# joystick.net
KiCad netlist of a schematic drawn in EAGLE
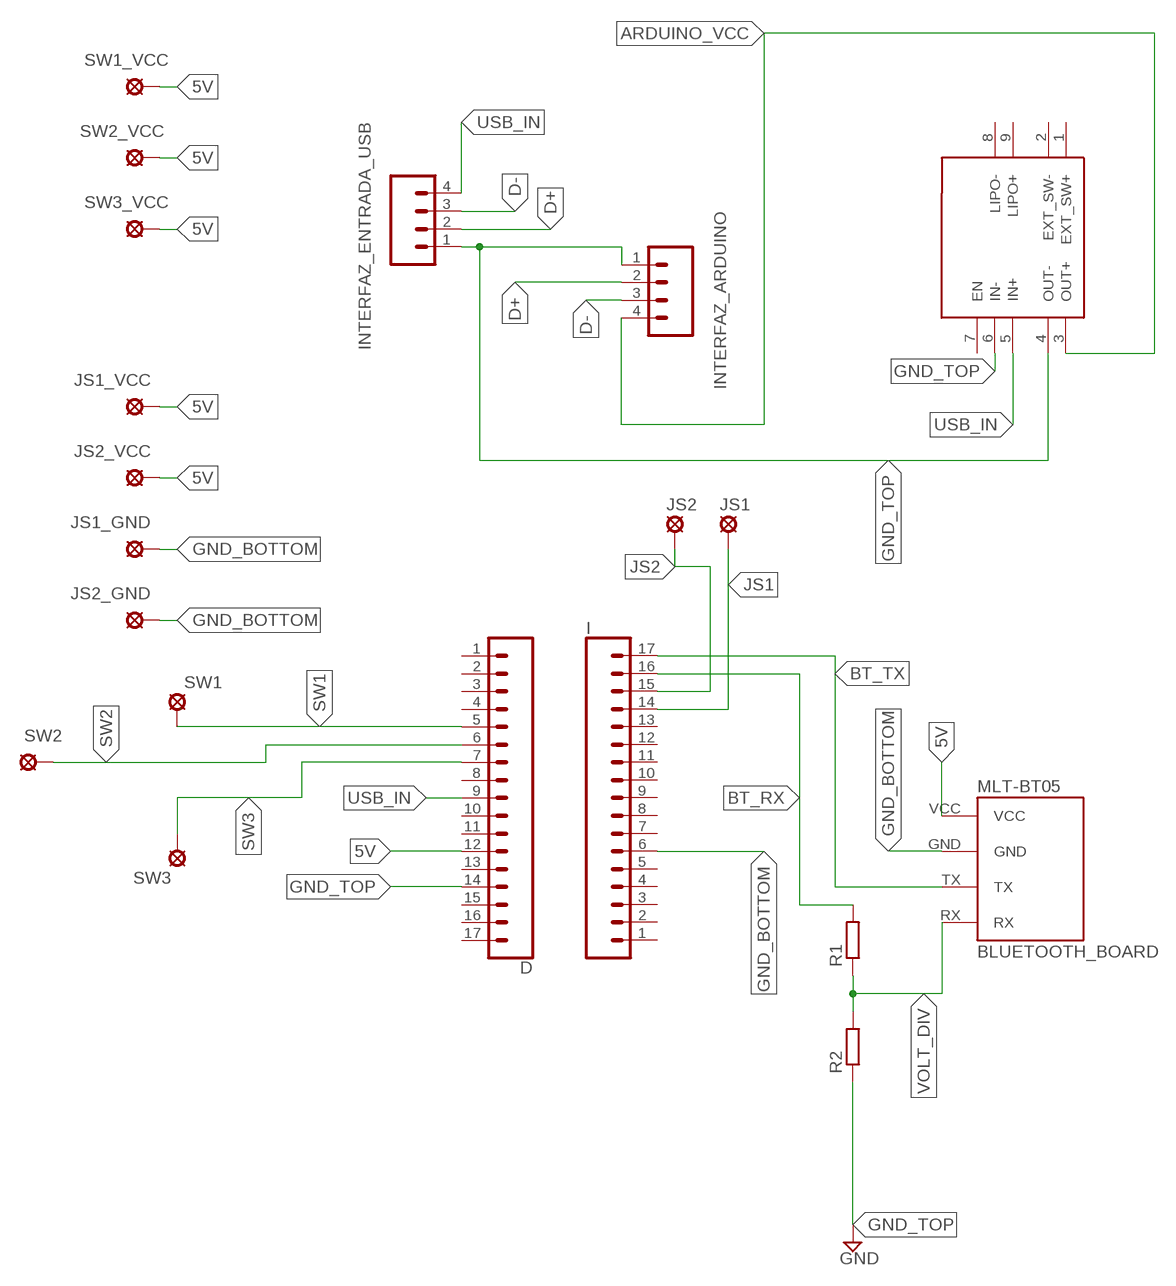
[diagram p0: schematic, sheet 1]

(export (version "E")
  (design (tool "Eeschema 10.0.6"))
  (components
    (comp (ref "D")
      (value "CONN_17")
      (footprint "eagle-import:1X17")
      (libsource (lib "eagle-import") (part "CONN_17"))
    )
    (comp (ref "I")
      (value "CONN_17")
      (footprint "eagle-import:1X17")
      (libsource (lib "eagle-import") (part "CONN_17"))
    )
    (comp (ref "INTERFAZ_ARDUINO")
      (value "CONN_04")
      (footprint "eagle-import:1X04")
      (libsource (lib "eagle-import") (part "CONN_04"))
    )
    (comp (ref "INTERFAZ_ENTRADA_USB")
      (value "CONN_04")
      (footprint "eagle-import:1X04")
      (libsource (lib "eagle-import") (part "CONN_04"))
    )
    (comp (ref "JS1")
      (value "MCS08")
      (footprint "eagle-import:MCS08")
      (libsource (lib "eagle-import") (part "MCS08"))
    )
    (comp (ref "JS1_GND")
      (value "MCS08")
      (footprint "eagle-import:MCS08")
      (libsource (lib "eagle-import") (part "MCS08"))
    )
    (comp (ref "JS1_VCC")
      (value "MCS08")
      (footprint "eagle-import:MCS08")
      (libsource (lib "eagle-import") (part "MCS08"))
    )
    (comp (ref "JS2")
      (value "MCS08")
      (footprint "eagle-import:MCS08")
      (libsource (lib "eagle-import") (part "MCS08"))
    )
    (comp (ref "JS2_GND")
      (value "MCS08")
      (footprint "eagle-import:MCS08")
      (libsource (lib "eagle-import") (part "MCS08"))
    )
    (comp (ref "JS2_VCC")
      (value "MCS08")
      (footprint "eagle-import:MCS08")
      (libsource (lib "eagle-import") (part "MCS08"))
    )
    (comp (ref "LIPO_BOOSTER")
      (value "LIP_CHARGER_LAYOUT")
      (footprint "eagle-import:LIP_CHARGER_FOOTPRINT")
      (libsource (lib "eagle-import") (part "LIP_CHARGER_LAYOUT"))
    )
    (comp (ref "MLT-BT05")
      (value "BLUETOOTH_BOARD")
      (footprint "eagle-import:BT_BOARD_FOOTPRINT")
      (libsource (lib "eagle-import") (part "BLUETOOTH_BOARD"))
    )
    (comp (ref "R1")
      (value "R-EU_R0805")
      (footprint "eagle-import:R0805")
      (libsource (lib "eagle-import") (part "R-EU_R0805"))
    )
    (comp (ref "R2")
      (value "R-EU_R0805")
      (footprint "eagle-import:R0805")
      (libsource (lib "eagle-import") (part "R-EU_R0805"))
    )
    (comp (ref "SW1")
      (value "MCS08")
      (footprint "eagle-import:MCS08")
      (libsource (lib "eagle-import") (part "MCS08"))
    )
    (comp (ref "SW1_VCC")
      (value "MCS08")
      (footprint "eagle-import:MCS08")
      (libsource (lib "eagle-import") (part "MCS08"))
    )
    (comp (ref "SW2")
      (value "MCS08")
      (footprint "eagle-import:MCS08")
      (libsource (lib "eagle-import") (part "MCS08"))
    )
    (comp (ref "SW2_VCC")
      (value "MCS08")
      (footprint "eagle-import:MCS08")
      (libsource (lib "eagle-import") (part "MCS08"))
    )
    (comp (ref "SW3")
      (value "MCS08")
      (footprint "eagle-import:MCS08")
      (libsource (lib "eagle-import") (part "MCS08"))
    )
    (comp (ref "SW3_VCC")
      (value "MCS08")
      (footprint "eagle-import:MCS08")
      (libsource (lib "eagle-import") (part "MCS08"))
    )
  )
  (nets
    (net (code "1") (name "5V") (class "Default")
      (node (ref "D") (pin "12") (pinfunction "12_12") (pintype "passive"))
      (node (ref "JS1_VCC") (pin "MP") (pinfunction "MP_MP") (pintype "passive"))
      (node (ref "JS2_VCC") (pin "MP") (pinfunction "MP_MP") (pintype "passive"))
      (node (ref "MLT-BT05") (pin "VCC") (pinfunction "VCC_VCC") (pintype "bidirectional"))
      (node (ref "SW1_VCC") (pin "MP") (pinfunction "MP_MP") (pintype "passive"))
      (node (ref "SW2_VCC") (pin "MP") (pinfunction "MP_MP") (pintype "passive"))
      (node (ref "SW3_VCC") (pin "MP") (pinfunction "MP_MP") (pintype "passive"))
    )
    (net (code "2") (name "ARDUINO_VCC") (class "Default")
      (node (ref "INTERFAZ_ARDUINO") (pin "4") (pinfunction "4_4") (pintype "passive"))
      (node (ref "LIPO_BOOSTER") (pin "3") (pinfunction "OUT+_3") (pintype "bidirectional"))
    )
    (net (code "3") (name "BT_RX") (class "Default")
      (node (ref "I") (pin "16") (pinfunction "16_16") (pintype "passive"))
      (node (ref "R1") (pin "2") (pinfunction "2_2") (pintype "passive"))
    )
    (net (code "4") (name "BT_TX") (class "Default")
      (node (ref "I") (pin "17") (pinfunction "17_17") (pintype "passive"))
      (node (ref "MLT-BT05") (pin "TX") (pinfunction "TX_TX") (pintype "bidirectional"))
    )
    (net (code "5") (name "D+") (class "Default")
      (node (ref "INTERFAZ_ARDUINO") (pin "2") (pinfunction "2_2") (pintype "passive"))
      (node (ref "INTERFAZ_ENTRADA_USB") (pin "2") (pinfunction "2_2") (pintype "passive"))
    )
    (net (code "6") (name "D-") (class "Default")
      (node (ref "INTERFAZ_ARDUINO") (pin "3") (pinfunction "3_3") (pintype "passive"))
      (node (ref "INTERFAZ_ENTRADA_USB") (pin "3") (pinfunction "3_3") (pintype "passive"))
    )
    (net (code "7") (name "GND_BOTTOM") (class "Default")
      (node (ref "I") (pin "6") (pinfunction "6_6") (pintype "passive"))
      (node (ref "JS1_GND") (pin "MP") (pinfunction "MP_MP") (pintype "passive"))
      (node (ref "JS2_GND") (pin "MP") (pinfunction "MP_MP") (pintype "passive"))
      (node (ref "MLT-BT05") (pin "GND") (pinfunction "GND_GND") (pintype "bidirectional"))
    )
    (net (code "8") (name "GND_TOP") (class "Default")
      (node (ref "D") (pin "14") (pinfunction "14_14") (pintype "passive"))
      (node (ref "INTERFAZ_ARDUINO") (pin "1") (pinfunction "1_1") (pintype "passive"))
      (node (ref "INTERFAZ_ENTRADA_USB") (pin "1") (pinfunction "1_1") (pintype "passive"))
      (node (ref "LIPO_BOOSTER") (pin "4") (pinfunction "OUT-_4") (pintype "bidirectional"))
      (node (ref "LIPO_BOOSTER") (pin "6") (pinfunction "IN-_6") (pintype "bidirectional"))
      (node (ref "R2") (pin "1") (pinfunction "1_1") (pintype "passive"))
    )
    (net (code "9") (name "JS1") (class "Default")
      (node (ref "I") (pin "14") (pinfunction "14_14") (pintype "passive"))
      (node (ref "JS1") (pin "MP") (pinfunction "MP_MP") (pintype "passive"))
    )
    (net (code "10") (name "JS2") (class "Default")
      (node (ref "I") (pin "15") (pinfunction "15_15") (pintype "passive"))
      (node (ref "JS2") (pin "MP") (pinfunction "MP_MP") (pintype "passive"))
    )
    (net (code "11") (name "SW1") (class "Default")
      (node (ref "D") (pin "5") (pinfunction "5_5") (pintype "passive"))
      (node (ref "SW1") (pin "MP") (pinfunction "MP_MP") (pintype "passive"))
    )
    (net (code "12") (name "SW2") (class "Default")
      (node (ref "D") (pin "6") (pinfunction "6_6") (pintype "passive"))
      (node (ref "SW2") (pin "MP") (pinfunction "MP_MP") (pintype "passive"))
    )
    (net (code "13") (name "SW3") (class "Default")
      (node (ref "D") (pin "7") (pinfunction "7_7") (pintype "passive"))
      (node (ref "SW3") (pin "MP") (pinfunction "MP_MP") (pintype "passive"))
    )
    (net (code "14") (name "USB_IN") (class "Default")
      (node (ref "D") (pin "9") (pinfunction "9_9") (pintype "passive"))
      (node (ref "INTERFAZ_ENTRADA_USB") (pin "4") (pinfunction "4_4") (pintype "passive"))
      (node (ref "LIPO_BOOSTER") (pin "5") (pinfunction "IN+_5") (pintype "bidirectional"))
    )
    (net (code "15") (name "VOLT_DIV") (class "Default")
      (node (ref "MLT-BT05") (pin "RX") (pinfunction "RX_RX") (pintype "bidirectional"))
      (node (ref "R1") (pin "1") (pinfunction "1_1") (pintype "passive"))
      (node (ref "R2") (pin "2") (pinfunction "2_2") (pintype "passive"))
    )
    (net (code "16") (name "unconnected-(D-Pad1)") (class "Default")
      (node (ref "D") (pin "1") (pinfunction "1_1") (pintype "passive"))
    )
    (net (code "17") (name "unconnected-(D-Pad2)") (class "Default")
      (node (ref "D") (pin "2") (pinfunction "2_2") (pintype "passive"))
    )
    (net (code "18") (name "unconnected-(D-Pad3)") (class "Default")
      (node (ref "D") (pin "3") (pinfunction "3_3") (pintype "passive"))
    )
    (net (code "19") (name "unconnected-(D-Pad4)") (class "Default")
      (node (ref "D") (pin "4") (pinfunction "4_4") (pintype "passive"))
    )
    (net (code "20") (name "unconnected-(D-Pad8)") (class "Default")
      (node (ref "D") (pin "8") (pinfunction "8_8") (pintype "passive"))
    )
    (net (code "21") (name "unconnected-(D-Pad10)") (class "Default")
      (node (ref "D") (pin "10") (pinfunction "10_10") (pintype "passive"))
    )
    (net (code "22") (name "unconnected-(D-Pad11)") (class "Default")
      (node (ref "D") (pin "11") (pinfunction "11_11") (pintype "passive"))
    )
    (net (code "23") (name "unconnected-(D-Pad13)") (class "Default")
      (node (ref "D") (pin "13") (pinfunction "13_13") (pintype "passive"))
    )
    (net (code "24") (name "unconnected-(D-Pad15)") (class "Default")
      (node (ref "D") (pin "15") (pinfunction "15_15") (pintype "passive"))
    )
    (net (code "25") (name "unconnected-(D-Pad16)") (class "Default")
      (node (ref "D") (pin "16") (pinfunction "16_16") (pintype "passive"))
    )
    (net (code "26") (name "unconnected-(D-Pad17)") (class "Default")
      (node (ref "D") (pin "17") (pinfunction "17_17") (pintype "passive"))
    )
    (net (code "27") (name "unconnected-(I-Pad1)") (class "Default")
      (node (ref "I") (pin "1") (pinfunction "1_1") (pintype "passive"))
    )
    (net (code "28") (name "unconnected-(I-Pad2)") (class "Default")
      (node (ref "I") (pin "2") (pinfunction "2_2") (pintype "passive"))
    )
    (net (code "29") (name "unconnected-(I-Pad3)") (class "Default")
      (node (ref "I") (pin "3") (pinfunction "3_3") (pintype "passive"))
    )
    (net (code "30") (name "unconnected-(I-Pad4)") (class "Default")
      (node (ref "I") (pin "4") (pinfunction "4_4") (pintype "passive"))
    )
    (net (code "31") (name "unconnected-(I-Pad5)") (class "Default")
      (node (ref "I") (pin "5") (pinfunction "5_5") (pintype "passive"))
    )
    (net (code "32") (name "unconnected-(I-Pad7)") (class "Default")
      (node (ref "I") (pin "7") (pinfunction "7_7") (pintype "passive"))
    )
    (net (code "33") (name "unconnected-(I-Pad8)") (class "Default")
      (node (ref "I") (pin "8") (pinfunction "8_8") (pintype "passive"))
    )
    (net (code "34") (name "unconnected-(I-Pad9)") (class "Default")
      (node (ref "I") (pin "9") (pinfunction "9_9") (pintype "passive"))
    )
    (net (code "35") (name "unconnected-(I-Pad10)") (class "Default")
      (node (ref "I") (pin "10") (pinfunction "10_10") (pintype "passive"))
    )
    (net (code "36") (name "unconnected-(I-Pad11)") (class "Default")
      (node (ref "I") (pin "11") (pinfunction "11_11") (pintype "passive"))
    )
    (net (code "37") (name "unconnected-(I-Pad12)") (class "Default")
      (node (ref "I") (pin "12") (pinfunction "12_12") (pintype "passive"))
    )
    (net (code "38") (name "unconnected-(I-Pad13)") (class "Default")
      (node (ref "I") (pin "13") (pinfunction "13_13") (pintype "passive"))
    )
    (net (code "39") (name "unconnected-(LIPO_BOOSTER-EN-Pad7)") (class "Default")
      (node (ref "LIPO_BOOSTER") (pin "7") (pinfunction "EN_7") (pintype "bidirectional"))
    )
    (net (code "40") (name "unconnected-(LIPO_BOOSTER-EXT_SW+-Pad1)") (class "Default")
      (node (ref "LIPO_BOOSTER") (pin "1") (pinfunction "EXT_SW+_1") (pintype "bidirectional"))
    )
    (net (code "41") (name "unconnected-(LIPO_BOOSTER-EXT_SW--Pad2)") (class "Default")
      (node (ref "LIPO_BOOSTER") (pin "2") (pinfunction "EXT_SW-_2") (pintype "bidirectional"))
    )
    (net (code "42") (name "unconnected-(LIPO_BOOSTER-LIPO+-Pad9)") (class "Default")
      (node (ref "LIPO_BOOSTER") (pin "9") (pinfunction "LIPO+_9") (pintype "bidirectional"))
    )
    (net (code "43") (name "unconnected-(LIPO_BOOSTER-LIPO--Pad8)") (class "Default")
      (node (ref "LIPO_BOOSTER") (pin "8") (pinfunction "LIPO-_8") (pintype "bidirectional"))
    )
  )
)
